# tx.net
KiCad netlist of a schematic drawn in EAGLE
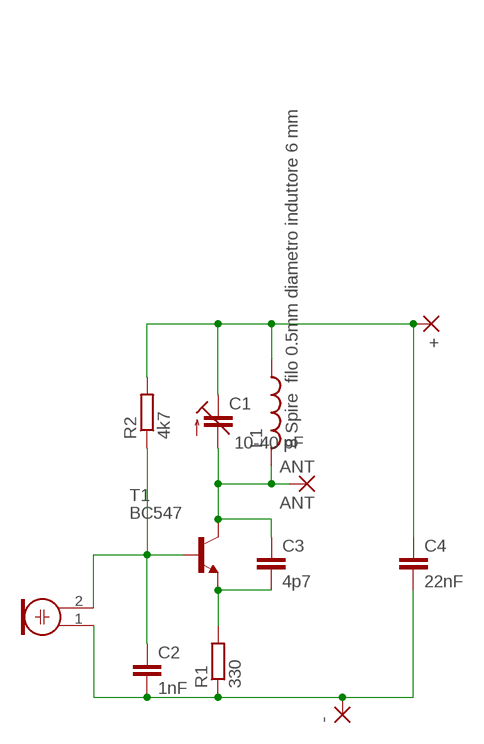
[diagram p0: schematic, sheet 1]

(export (version "E")
  (design (tool "Eeschema 10.0.6"))
  (components
    (comp (ref "+")
      (value "1,6/0,8")
      (footprint "eagle-import:1,6_0,8")
      (libsource (lib "eagle-import") (part "1,6/0,8"))
    )
    (comp (ref "-")
      (value "1,6/0,8")
      (footprint "eagle-import:1,6_0,8")
      (libsource (lib "eagle-import") (part "1,6/0,8"))
    )
    (comp (ref "ANT")
      (value "ANT")
      (footprint "eagle-import:1,6_0,8")
      (libsource (lib "eagle-import") (part "1,6/0,8"))
    )
    (comp (ref "C1")
      (value "10-40 pF")
      (footprint "eagle-import:3008")
      (libsource (lib "eagle-import") (part "C-TRIMM3008"))
    )
    (comp (ref "C2")
      (value "1nF")
      (footprint "eagle-import:C025-024X044")
      (libsource (lib "eagle-import") (part "C-EU025-024X044"))
    )
    (comp (ref "C3")
      (value "4p7")
      (footprint "eagle-import:C025-024X044")
      (libsource (lib "eagle-import") (part "C-EU025-024X044"))
    )
    (comp (ref "C4")
      (value "22nF")
      (footprint "eagle-import:C025-024X044")
      (libsource (lib "eagle-import") (part "C-EU025-024X044"))
    )
    (comp (ref "L1")
      (value "8 Spire filo 0.5mm diametro induttore 6 mm")
      (footprint "eagle-import:0207_10")
      (libsource (lib "eagle-import") (part "L-US0207/10"))
    )
    (comp (ref "M1")
      (value "ELECTRET_MICROPHON-F6050AP")
      (footprint "eagle-import:F6050AP")
      (libsource (lib "eagle-import") (part "ELECTRET_MICROPHON-F6050AP"))
    )
    (comp (ref "R1")
      (value "330")
      (footprint "eagle-import:0207_2V")
      (libsource (lib "eagle-import") (part "R-EU_0207/2V"))
    )
    (comp (ref "R2")
      (value "4k7")
      (footprint "eagle-import:0207_2V")
      (libsource (lib "eagle-import") (part "R-EU_0207/2V"))
    )
    (comp (ref "T1")
      (value "BC547")
      (footprint "eagle-import:TO92")
      (libsource (lib "eagle-import") (part "BC547"))
    )
  )
  (nets
    (net (code "1") (name "Net-(+-P)") (class "Default")
      (node (ref "+") (pin "1") (pinfunction "P_1") (pintype "passive"))
      (node (ref "C1") (pin "+") (pinfunction "E_+") (pintype "passive"))
      (node (ref "C4") (pin "1") (pinfunction "1_1") (pintype "passive"))
      (node (ref "L1") (pin "1") (pinfunction "1_1") (pintype "passive"))
      (node (ref "R2") (pin "2") (pinfunction "2_2") (pintype "passive"))
    )
    (net (code "2") (name "Net-(--P)") (class "Default")
      (node (ref "-") (pin "1") (pinfunction "P_1") (pintype "passive"))
      (node (ref "C2") (pin "2") (pinfunction "2_2") (pintype "passive"))
      (node (ref "C4") (pin "2") (pinfunction "2_2") (pintype "passive"))
      (node (ref "M1") (pin "1") (pinfunction "1_1") (pintype "passive"))
      (node (ref "R1") (pin "1") (pinfunction "1_1") (pintype "passive"))
    )
    (net (code "3") (name "Net-(ANT-P)") (class "Default")
      (node (ref "ANT") (pin "1") (pinfunction "P_1") (pintype "passive"))
      (node (ref "C1") (pin "-") (pinfunction "A_-") (pintype "passive"))
      (node (ref "C3") (pin "1") (pinfunction "1_1") (pintype "passive"))
      (node (ref "L1") (pin "2") (pinfunction "2_2") (pintype "passive"))
      (node (ref "T1") (pin "3") (pinfunction "C_3") (pintype "passive"))
    )
    (net (code "4") (name "Net-(T1-B)") (class "Default")
      (node (ref "C2") (pin "1") (pinfunction "1_1") (pintype "passive"))
      (node (ref "M1") (pin "2") (pinfunction "2_2") (pintype "passive"))
      (node (ref "R2") (pin "1") (pinfunction "1_1") (pintype "passive"))
      (node (ref "T1") (pin "2") (pinfunction "B_2") (pintype "passive"))
    )
    (net (code "5") (name "Net-(T1-E)") (class "Default")
      (node (ref "C3") (pin "2") (pinfunction "2_2") (pintype "passive"))
      (node (ref "R1") (pin "2") (pinfunction "2_2") (pintype "passive"))
      (node (ref "T1") (pin "1") (pinfunction "E_1") (pintype "passive"))
    )
  )
)
